# Sensors_Board.net
KiCad netlist of a schematic drawn in Altium Designer
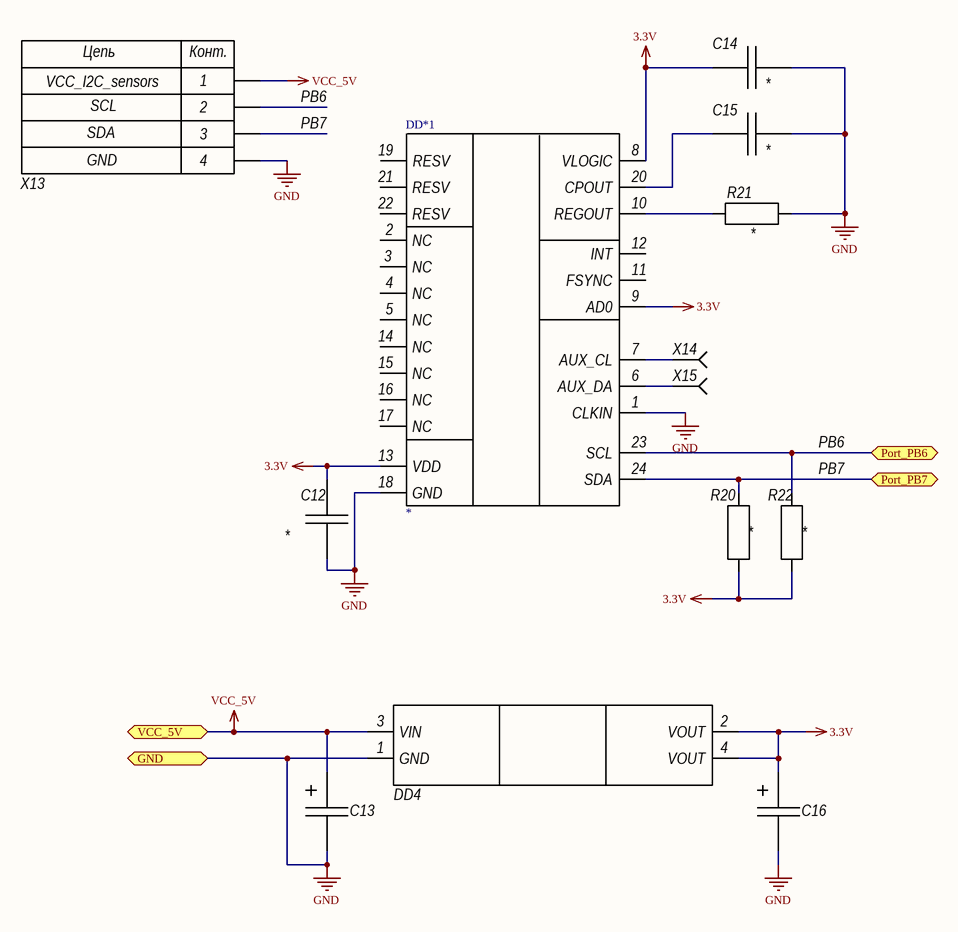
[diagram p0: Sensors_Board.SchDoc]

(export (version "E")
  (design (tool "Eeschema 10.0.6"))
  (components
    (comp (ref "C12")
      (value "*")
      (footprint "CAP EIA 0805")
      (fields (field (name "ALTIUM_VALUE") "*"))
      (libsource (lib "Capacitors") (part "Cap EIA 0805"))
    )
    (comp (ref "C13")
      (value "Cap El Case A (Tantalum)")
      (footprint "CAP CASE A")
      (libsource (lib "Capacitors") (part "Cap El Case A (Tantalum)"))
    )
    (comp (ref "C14")
      (value "*")
      (footprint "CAP EIA 0805")
      (fields (field (name "ALTIUM_VALUE") "*"))
      (libsource (lib "Capacitors") (part "Cap EIA 0805"))
    )
    (comp (ref "C15")
      (value "*")
      (footprint "CAP EIA 0805")
      (fields (field (name "ALTIUM_VALUE") "*"))
      (libsource (lib "Capacitors") (part "Cap EIA 0805"))
    )
    (comp (ref "C16")
      (value "Cap El Case A (Tantalum)")
      (footprint "CAP CASE A")
      (libsource (lib "Capacitors") (part "Cap El Case A (Tantalum)"))
    )
    (comp (ref "DD*1")
      (value "*")
      (footprint "(MPU60-x0)QNF24 4*4*0.9")
      (description "MPU-60X0 is the device that combines a 3-axis  gyroscope, 3-axis accelerometer")
      (libsource (lib "Integrated_Circuits") (part "MPU6050"))
    )
    (comp (ref "DD4")
      (value "LM1117S50")
      (footprint "SOT-223_M")
      (description "LDO Voltage Regulator")
      (fields (field (name "MANUFACTURER") "ST Microelectronics"))
      (libsource (lib "Integrated_Circuits") (part "LM1117S50"))
    )
    (comp (ref "R20")
      (value "*")
      (footprint "RES EIA 0805")
      (fields (field (name "ALTIUM_VALUE") "*"))
      (libsource (lib "Resistors") (part "Res EIA 0805"))
    )
    (comp (ref "R21")
      (value "*")
      (footprint "RES EIA 0805")
      (fields (field (name "ALTIUM_VALUE") "*"))
      (libsource (lib "Resistors") (part "Res EIA 0805"))
    )
    (comp (ref "R22")
      (value "*")
      (footprint "RES EIA 0805")
      (fields (field (name "ALTIUM_VALUE") "*"))
      (libsource (lib "Resistors") (part "Res EIA 0805"))
    )
    (comp (ref "X13")
      (value "~")
      (footprint "SWD")
      (fields (field (name "MANUFACTURER") "Hsuan Mao(Китай)"))
      (libsource (lib "Connectors") (part "PLS-4"))
    )
    (comp (ref "X14")
      (value "*")
      (footprint "Pin - Referal")
      (description "Generic Pin Contact")
      (libsource (lib "Connectors") (part "Pin_Referal"))
    )
    (comp (ref "X15")
      (value "*")
      (footprint "Pin - Referal")
      (description "Generic Pin Contact")
      (libsource (lib "Connectors") (part "Pin_Referal"))
    )
  )
  (nets
    (net (code "1") (name "/PB6") (class "Default")
      (node (ref "DD*1") (pin "23") (pinfunction "SCL_23") (pintype "passive"))
      (node (ref "R22") (pin "2") (pinfunction "2_2") (pintype "passive"))
      (node (ref "X13") (pin "2") (pinfunction "2_2") (pintype "passive"))
    )
    (net (code "2") (name "/PB7") (class "Default")
      (node (ref "DD*1") (pin "24") (pinfunction "SDA_24") (pintype "passive"))
      (node (ref "R20") (pin "1") (pinfunction "1_1") (pintype "passive"))
      (node (ref "X13") (pin "3") (pinfunction "3_3") (pintype "passive"))
    )
    (net (code "3") (name "3.3V") (class "Default")
      (node (ref "C12") (pin "1") (pinfunction "1_1") (pintype "passive"))
      (node (ref "C14") (pin "1") (pinfunction "1_1") (pintype "passive"))
      (node (ref "C16") (pin "1") (pinfunction "1_1") (pintype "passive"))
      (node (ref "DD*1") (pin "13") (pinfunction "VDD_13") (pintype "passive"))
      (node (ref "DD*1") (pin "8") (pinfunction "VLOGIC_8") (pintype "passive"))
      (node (ref "DD*1") (pin "9") (pinfunction "AD0_9") (pintype "passive"))
      (node (ref "DD4") (pin "2") (pinfunction "VOUT_2") (pintype "passive"))
      (node (ref "DD4") (pin "4") (pinfunction "VOUT_4") (pintype "passive"))
      (node (ref "R20") (pin "2") (pinfunction "2_2") (pintype "passive"))
      (node (ref "R22") (pin "1") (pinfunction "1_1") (pintype "passive"))
    )
    (net (code "4") (name "GND") (class "Default")
      (node (ref "C12") (pin "2") (pinfunction "2_2") (pintype "passive"))
      (node (ref "C13") (pin "2") (pinfunction "2_2") (pintype "passive"))
      (node (ref "C14") (pin "2") (pinfunction "2_2") (pintype "passive"))
      (node (ref "C15") (pin "2") (pinfunction "2_2") (pintype "passive"))
      (node (ref "C16") (pin "2") (pinfunction "2_2") (pintype "passive"))
      (node (ref "DD*1") (pin "1") (pinfunction "CLKIN_1") (pintype "passive"))
      (node (ref "DD*1") (pin "18") (pinfunction "GND_18") (pintype "passive"))
      (node (ref "DD4") (pin "1") (pinfunction "GND_1") (pintype "passive"))
      (node (ref "R21") (pin "1") (pinfunction "1_1") (pintype "passive"))
      (node (ref "X13") (pin "4") (pinfunction "4_4") (pintype "passive"))
    )
    (net (code "5") (name "Net-(DD*1-AUX_CL)") (class "Default")
      (node (ref "DD*1") (pin "7") (pinfunction "AUX_CL_7") (pintype "passive"))
      (node (ref "X14") (pin "1") (pinfunction "1_1") (pintype "passive"))
    )
    (net (code "6") (name "Net-(DD*1-AUX_DA)") (class "Default")
      (node (ref "DD*1") (pin "6") (pinfunction "AUX_DA_6") (pintype "passive"))
      (node (ref "X15") (pin "1") (pinfunction "1_1") (pintype "passive"))
    )
    (net (code "7") (name "Net-(DD*1-CPOUT)") (class "Default")
      (node (ref "C15") (pin "1") (pinfunction "1_1") (pintype "passive"))
      (node (ref "DD*1") (pin "20") (pinfunction "CPOUT_20") (pintype "passive"))
    )
    (net (code "8") (name "Net-(DD*1-REGOUT)") (class "Default")
      (node (ref "DD*1") (pin "10") (pinfunction "REGOUT_10") (pintype "passive"))
      (node (ref "R21") (pin "2") (pinfunction "2_2") (pintype "passive"))
    )
    (net (code "9") (name "VCC_5V") (class "Default")
      (node (ref "C13") (pin "1") (pinfunction "1_1") (pintype "passive"))
      (node (ref "DD4") (pin "3") (pinfunction "VIN_3") (pintype "passive"))
      (node (ref "X13") (pin "1") (pinfunction "1_1") (pintype "passive"))
    )
    (net (code "10") (name "unconnected-(DD*1-FSYNC-Pad11)") (class "Default")
      (node (ref "DD*1") (pin "11") (pinfunction "FSYNC_11") (pintype "passive"))
    )
    (net (code "11") (name "unconnected-(DD*1-INT-Pad12)") (class "Default")
      (node (ref "DD*1") (pin "12") (pinfunction "INT_12") (pintype "passive"))
    )
    (net (code "12") (name "unconnected-(DD*1-NC-Pad2)") (class "Default")
      (node (ref "DD*1") (pin "2") (pinfunction "NC_2") (pintype "passive"))
    )
    (net (code "13") (name "unconnected-(DD*1-NC-Pad3)") (class "Default")
      (node (ref "DD*1") (pin "3") (pinfunction "NC_3") (pintype "passive"))
    )
    (net (code "14") (name "unconnected-(DD*1-NC-Pad4)") (class "Default")
      (node (ref "DD*1") (pin "4") (pinfunction "NC_4") (pintype "passive"))
    )
    (net (code "15") (name "unconnected-(DD*1-NC-Pad5)") (class "Default")
      (node (ref "DD*1") (pin "5") (pinfunction "NC_5") (pintype "passive"))
    )
    (net (code "16") (name "unconnected-(DD*1-NC-Pad14)") (class "Default")
      (node (ref "DD*1") (pin "14") (pinfunction "NC_14") (pintype "passive"))
    )
    (net (code "17") (name "unconnected-(DD*1-NC-Pad15)") (class "Default")
      (node (ref "DD*1") (pin "15") (pinfunction "NC_15") (pintype "passive"))
    )
    (net (code "18") (name "unconnected-(DD*1-NC-Pad16)") (class "Default")
      (node (ref "DD*1") (pin "16") (pinfunction "NC_16") (pintype "passive"))
    )
    (net (code "19") (name "unconnected-(DD*1-NC-Pad17)") (class "Default")
      (node (ref "DD*1") (pin "17") (pinfunction "NC_17") (pintype "passive"))
    )
    (net (code "20") (name "unconnected-(DD*1-RESV-Pad19)") (class "Default")
      (node (ref "DD*1") (pin "19") (pinfunction "RESV_19") (pintype "passive"))
    )
    (net (code "21") (name "unconnected-(DD*1-RESV-Pad21)") (class "Default")
      (node (ref "DD*1") (pin "21") (pinfunction "RESV_21") (pintype "passive"))
    )
    (net (code "22") (name "unconnected-(DD*1-RESV-Pad22)") (class "Default")
      (node (ref "DD*1") (pin "22") (pinfunction "RESV_22") (pintype "passive"))
    )
  )
)
